# SAM4s_Schematic.net
KiCad netlist of a schematic drawn in Altium Designer
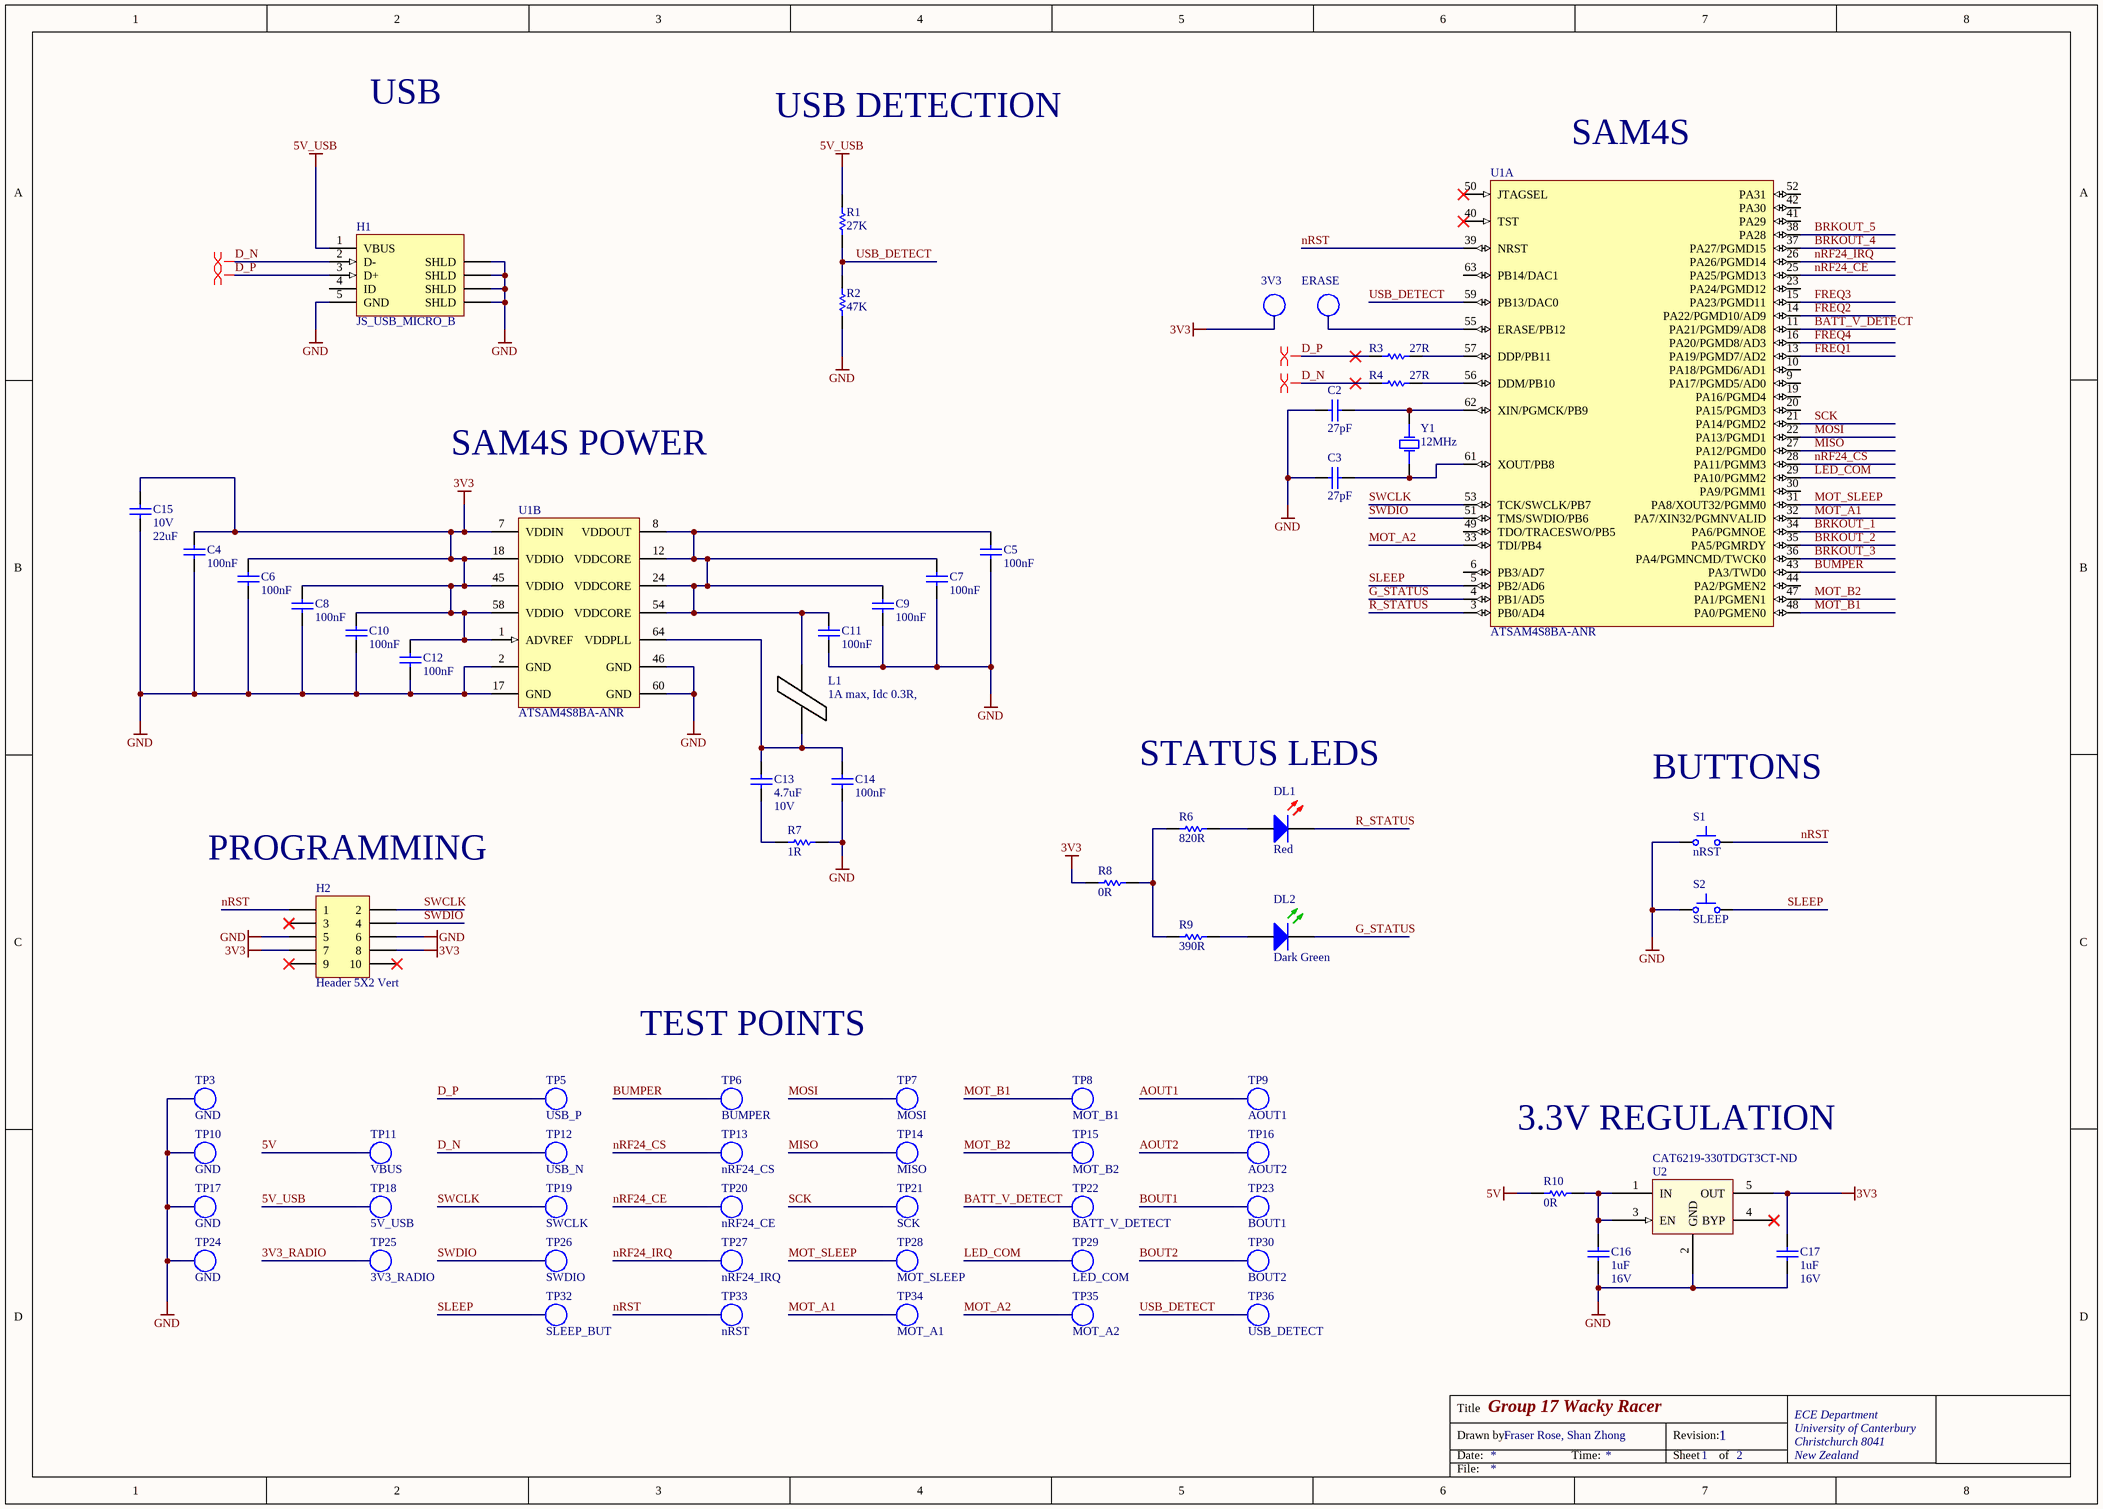
[diagram p0: SAM4s_Schematic.SchDoc]

(export (version "E")
  (design (tool "Eeschema 10.0.6"))
  (components
    (comp (ref "C2")
      (value "27pF")
      (footprint "CAPC1608N")
      (description "CAP CER 27pF NPO/COG +-5% 50V 0603")
      (libsource (lib "ECE AD19Components_19V1") (part "CC_27pF_0603"))
    )
    (comp (ref "C3")
      (value "27pF")
      (footprint "CAPC1608N")
      (description "CAP CER 27pF NPO/COG +-5% 50V 0603")
      (libsource (lib "ECE AD19Components_19V1") (part "CC_27pF_0603"))
    )
    (comp (ref "C4")
      (value "100nF")
      (footprint "CAPC1608N")
      (description "CAP CER 100nF X7R +-10% 50V 0603")
      (libsource (lib "ECE AD19Components_19V1") (part "CC_100nF_0603"))
    )
    (comp (ref "C5")
      (value "100nF")
      (footprint "CAPC1608N")
      (description "CAP CER 100nF X7R +-10% 50V 0603")
      (libsource (lib "ECE AD19Components_19V1") (part "CC_100nF_0603"))
    )
    (comp (ref "C6")
      (value "100nF")
      (footprint "CAPC1608N")
      (description "CAP CER 100nF X7R +-10% 50V 0603")
      (libsource (lib "ECE AD19Components_19V1") (part "CC_100nF_0603"))
    )
    (comp (ref "C7")
      (value "100nF")
      (footprint "CAPC1608N")
      (description "CAP CER 100nF X7R +-10% 50V 0603")
      (libsource (lib "ECE AD19Components_19V1") (part "CC_100nF_0603"))
    )
    (comp (ref "C8")
      (value "100nF")
      (footprint "CAPC1608N")
      (description "CAP CER 100nF X7R +-10% 50V 0603")
      (libsource (lib "ECE AD19Components_19V1") (part "CC_100nF_0603"))
    )
    (comp (ref "C9")
      (value "100nF")
      (footprint "CAPC1608N")
      (description "CAP CER 100nF X7R +-10% 50V 0603")
      (libsource (lib "ECE AD19Components_19V1") (part "CC_100nF_0603"))
    )
    (comp (ref "C10")
      (value "100nF")
      (footprint "CAPC1608N")
      (description "CAP CER 100nF X7R +-10% 50V 0603")
      (libsource (lib "ECE AD19Components_19V1") (part "CC_100nF_0603"))
    )
    (comp (ref "C11")
      (value "100nF")
      (footprint "CAPC1608N")
      (description "CAP CER 100nF X7R +-10% 50V 0603")
      (libsource (lib "ECE AD19Components_19V1") (part "CC_100nF_0603"))
    )
    (comp (ref "C12")
      (value "100nF")
      (footprint "CAPC1608N")
      (description "CAP CER 100nF X7R +-10% 50V 0603")
      (libsource (lib "ECE AD19Components_19V1") (part "CC_100nF_0603"))
    )
    (comp (ref "C13")
      (value "4.7uF")
      (footprint "CAPC1608N")
      (description "CAP CER 4.7uF X5R +-20%  10V 0603")
      (fields (field (name "MAX VOLTAGE") "10V"))
      (libsource (lib "ECE AD19Components_19V1") (part "CC_4.7uF_0603"))
    )
    (comp (ref "C14")
      (value "100nF")
      (footprint "CAPC1608N")
      (description "CAP CER 100nF X7R +-10% 50V 0603")
      (libsource (lib "ECE AD19Components_19V1") (part "CC_100nF_0603"))
    )
    (comp (ref "C15")
      (value "22uF")
      (footprint "CAPC3216N")
      (description "CAP CER 22uF Y5V -20% +80% 10V 1206")
      (fields (field (name "MAX VOLTAGE") "10V"))
      (libsource (lib "ECE AD19Components_19V1") (part "CC_22uF_1206"))
    )
    (comp (ref "C16")
      (value "1uF")
      (footprint "CAPC1608N")
      (description "CAP CER 1uF Y5V -20% +80% 16V 0603")
      (fields (field (name "MAX VOLTAGE") "16V"))
      (libsource (lib "ECE AD19Components_19V1") (part "CC_1uF_0603"))
    )
    (comp (ref "C17")
      (value "1uF")
      (footprint "CAPC1608N")
      (description "CAP CER 1uF Y5V -20% +80% 16V 0603")
      (fields (field (name "MAX VOLTAGE") "16V"))
      (libsource (lib "ECE AD19Components_19V1") (part "CC_1uF_0603"))
    )
    (comp (ref "DL1")
      (value "Red")
      (footprint "WL-SMCW0603")
      (description "LED Red 250mcd 0603 SMD")
      (fields
        (field (name "MANUFACTURER") "WURTH ELEKTRONIK")
        (field (name "MANUFACTURER PART NUMBER") "150060RS75000")
        (field (name "LED COLOUR") "Red")
      )
      (libsource (lib "ECE AD19Components_19V1") (part "DL_150060RS75000"))
    )
    (comp (ref "DL2")
      (value "Dark Green")
      (footprint "WL-SMCW0603")
      (description "LED Dk Green 430mcd 0603 SMD")
      (fields
        (field (name "MANUFACTURER") "WURTH ELEKTRONIK")
        (field (name "MANUFACTURER PART NUMBER") "150060GS75000")
        (field (name "LED COLOUR") "Dark Green")
      )
      (libsource (lib "ECE AD19Components_19V1") (part "DL_150060GS75000"))
    )
    (comp (ref "H1")
      (value "JS_USB_MICRO_B")
      (footprint "FCI_USB_10118194-0001LF")
      (description "CONN USB MICRO B RECPT SMT R/A")
      (fields (field (name "MANUFACTURER") "FCI") (field (name "MANUFACTURER PART NUMBER") "10118194-0001LF"))
      (libsource (lib "ECE AD19Components_19V1") (part "JS_USB_MICRO_B_SMT"))
    )
    (comp (ref "H2")
      (value "Header 5X2 Vert")
      (footprint "IDC2.54-V10D")
      (description "IDC Header, 2,54mm, 10-Pin, Vert")
      (libsource (lib "ECE AD19Components_19V1") (part "JA_HDR_IDC_5X2_VERT"))
    )
    (comp (ref "L1")
      (value "1A max, Idc 0.3R,")
      (footprint "INDC3216N")
      (description "Ferrite Bead, Rdc 0.3R, Z100MHZ 600R, Imax 1A, SMD 1206")
      (fields
        (field (name "MANUFACTURER") "FAIR-RITE")
        (field (name "MANUFACTURER PART NUMBER") "2512066017Y1")
      )
      (libsource (lib "ECE AD19Components_19V1") (part "IN_Ferrite-Bead"))
    )
    (comp (ref "R1")
      (value "27K")
      (footprint "RESC1608N")
      (description "RES 27K OHM 1/10W 5% 0603 SMD")
      (libsource (lib "ECE AD19Components_19V1") (part "RS_27K"))
    )
    (comp (ref "R2")
      (value "47K")
      (footprint "RESC1608N")
      (description "RES 47.0K OHM 1/10W 5% 0603 SMD")
      (libsource (lib "ECE AD19Components_19V1") (part "RS_47K"))
    )
    (comp (ref "R3")
      (value "27R")
      (footprint "RESC1608N")
      (description "RES 27 OHM 1/10W 5% 0603 SMD")
      (libsource (lib "ECE AD19Components_19V1") (part "RS_27R"))
    )
    (comp (ref "R4")
      (value "27R")
      (footprint "RESC1608N")
      (description "RES 27 OHM 1/10W 5% 0603 SMD")
      (libsource (lib "ECE AD19Components_19V1") (part "RS_27R"))
    )
    (comp (ref "R6")
      (value "820R")
      (footprint "RESC1608N")
      (description "RES 820 OHM 1/10W 5% 0603 SMD")
      (libsource (lib "ECE AD19Components_19V1") (part "RS_820R"))
    )
    (comp (ref "R7")
      (value "1R")
      (footprint "RESC3216N")
      (description "RES 1R OHM 1/4W 5% 1206 SMD")
      (libsource (lib "ECE AD19Components_19V1") (part "RT_1R"))
    )
    (comp (ref "R8")
      (value "0R")
      (footprint "RESC1608N")
      (description "RES 0.0 OHM 1/10W 5% 0603 SMD")
      (libsource (lib "ECE AD19Components_19V1") (part "RS_0R0"))
    )
    (comp (ref "R9")
      (value "390R")
      (footprint "RESC1608N")
      (description "RES 390 OHM 1/10W 5% 0603 SMD")
      (libsource (lib "ECE AD19Components_19V1") (part "RS_390R"))
    )
    (comp (ref "R10")
      (value "0R")
      (footprint "RESC1608N")
      (description "RES 0.0 OHM 1/10W 5% 0603 SMD")
      (libsource (lib "ECE AD19Components_19V1") (part "RS_0R0"))
    )
    (comp (ref "S1")
      (value "nRST")
      (footprint "EVQPNF05M")
      (description "Panasonic 6 x 3.5mm SMD Light Touch Switch Type SMD")
      (fields (field (name "MANUFACTURER") "Panasonic"))
      (libsource (lib "ECE AD19Components_19V1") (part "WS_EVQPNF05M"))
    )
    (comp (ref "S2")
      (value "SLEEP")
      (footprint "EVQPNF05M")
      (description "Panasonic 6 x 3.5mm SMD Light Touch Switch Type SMD")
      (fields (field (name "MANUFACTURER") "Panasonic"))
      (libsource (lib "ECE AD19Components_19V1") (part "WS_EVQPNF05M"))
    )
    (comp (ref "TP1")
      (value "3V3")
      (footprint "TP_0603")
      (description "Test Point 1.65X0.9X1.2mm SMD")
      (fields
        (field (name "MANUFACTURER") "TE Connectivity AMP Connectors")
        (field (name "MANUFACTURER PART NUMBER") "1625854-3")
      )
      (libsource (lib "ECE AD19Components_19V1") (part "TP_0603"))
    )
    (comp (ref "TP2")
      (value "ERASE")
      (footprint "TP_0603")
      (description "Test Point 1.65X0.9X1.2mm SMD")
      (fields
        (field (name "MANUFACTURER") "TE Connectivity AMP Connectors")
        (field (name "MANUFACTURER PART NUMBER") "1625854-3")
      )
      (libsource (lib "ECE AD19Components_19V1") (part "TP_0603"))
    )
    (comp (ref "TP3")
      (value "GND")
      (footprint "TP_0603")
      (description "Test Point 1.65X0.9X1.2mm SMD")
      (fields
        (field (name "MANUFACTURER") "TE Connectivity AMP Connectors")
        (field (name "MANUFACTURER PART NUMBER") "1625854-3")
      )
      (libsource (lib "ECE AD19Components_19V1") (part "TP_0603"))
    )
    (comp (ref "TP5")
      (value "USB_P")
      (footprint "TP_0603")
      (description "Test Point 1.65X0.9X1.2mm SMD")
      (fields
        (field (name "MANUFACTURER") "TE Connectivity AMP Connectors")
        (field (name "MANUFACTURER PART NUMBER") "1625854-3")
      )
      (libsource (lib "ECE AD19Components_19V1") (part "TP_0603"))
    )
    (comp (ref "TP6")
      (value "BUMPER")
      (footprint "TP_0603")
      (description "Test Point 1.65X0.9X1.2mm SMD")
      (fields
        (field (name "MANUFACTURER") "TE Connectivity AMP Connectors")
        (field (name "MANUFACTURER PART NUMBER") "1625854-3")
      )
      (libsource (lib "ECE AD19Components_19V1") (part "TP_0603"))
    )
    (comp (ref "TP7")
      (value "MOSI")
      (footprint "TP_0603")
      (description "Test Point 1.65X0.9X1.2mm SMD")
      (fields
        (field (name "MANUFACTURER") "TE Connectivity AMP Connectors")
        (field (name "MANUFACTURER PART NUMBER") "1625854-3")
      )
      (libsource (lib "ECE AD19Components_19V1") (part "TP_0603"))
    )
    (comp (ref "TP8")
      (value "MOT_B1")
      (footprint "TP_0603")
      (description "Test Point 1.65X0.9X1.2mm SMD")
      (fields
        (field (name "MANUFACTURER") "TE Connectivity AMP Connectors")
        (field (name "MANUFACTURER PART NUMBER") "1625854-3")
      )
      (libsource (lib "ECE AD19Components_19V1") (part "TP_0603"))
    )
    (comp (ref "TP9")
      (value "AOUT1")
      (footprint "TP_0603")
      (description "Test Point 1.65X0.9X1.2mm SMD")
      (fields
        (field (name "MANUFACTURER") "TE Connectivity AMP Connectors")
        (field (name "MANUFACTURER PART NUMBER") "1625854-3")
      )
      (libsource (lib "ECE AD19Components_19V1") (part "TP_0603"))
    )
    (comp (ref "TP10")
      (value "GND")
      (footprint "TP_0603")
      (description "Test Point 1.65X0.9X1.2mm SMD")
      (fields
        (field (name "MANUFACTURER") "TE Connectivity AMP Connectors")
        (field (name "MANUFACTURER PART NUMBER") "1625854-3")
      )
      (libsource (lib "ECE AD19Components_19V1") (part "TP_0603"))
    )
    (comp (ref "TP11")
      (value "VBUS")
      (footprint "TP_0603")
      (description "Test Point 1.65X0.9X1.2mm SMD")
      (fields
        (field (name "MANUFACTURER") "TE Connectivity AMP Connectors")
        (field (name "MANUFACTURER PART NUMBER") "1625854-3")
      )
      (libsource (lib "ECE AD19Components_19V1") (part "TP_0603"))
    )
    (comp (ref "TP12")
      (value "USB_N")
      (footprint "TP_0603")
      (description "Test Point 1.65X0.9X1.2mm SMD")
      (fields
        (field (name "MANUFACTURER") "TE Connectivity AMP Connectors")
        (field (name "MANUFACTURER PART NUMBER") "1625854-3")
      )
      (libsource (lib "ECE AD19Components_19V1") (part "TP_0603"))
    )
    (comp (ref "TP13")
      (value "nRF24_CS")
      (footprint "TP_0603")
      (description "Test Point 1.65X0.9X1.2mm SMD")
      (fields
        (field (name "MANUFACTURER") "TE Connectivity AMP Connectors")
        (field (name "MANUFACTURER PART NUMBER") "1625854-3")
      )
      (libsource (lib "ECE AD19Components_19V1") (part "TP_0603"))
    )
    (comp (ref "TP14")
      (value "MISO")
      (footprint "TP_0603")
      (description "Test Point 1.65X0.9X1.2mm SMD")
      (fields
        (field (name "MANUFACTURER") "TE Connectivity AMP Connectors")
        (field (name "MANUFACTURER PART NUMBER") "1625854-3")
      )
      (libsource (lib "ECE AD19Components_19V1") (part "TP_0603"))
    )
    (comp (ref "TP15")
      (value "MOT_B2")
      (footprint "TP_0603")
      (description "Test Point 1.65X0.9X1.2mm SMD")
      (fields
        (field (name "MANUFACTURER") "TE Connectivity AMP Connectors")
        (field (name "MANUFACTURER PART NUMBER") "1625854-3")
      )
      (libsource (lib "ECE AD19Components_19V1") (part "TP_0603"))
    )
    (comp (ref "TP16")
      (value "AOUT2")
      (footprint "TP_0603")
      (description "Test Point 1.65X0.9X1.2mm SMD")
      (fields
        (field (name "MANUFACTURER") "TE Connectivity AMP Connectors")
        (field (name "MANUFACTURER PART NUMBER") "1625854-3")
      )
      (libsource (lib "ECE AD19Components_19V1") (part "TP_0603"))
    )
    (comp (ref "TP17")
      (value "GND")
      (footprint "TP_0603")
      (description "Test Point 1.65X0.9X1.2mm SMD")
      (fields
        (field (name "MANUFACTURER") "TE Connectivity AMP Connectors")
        (field (name "MANUFACTURER PART NUMBER") "1625854-3")
      )
      (libsource (lib "ECE AD19Components_19V1") (part "TP_0603"))
    )
    (comp (ref "TP18")
      (value "5V_USB")
      (footprint "TP_0603")
      (description "Test Point 1.65X0.9X1.2mm SMD")
      (fields
        (field (name "MANUFACTURER") "TE Connectivity AMP Connectors")
        (field (name "MANUFACTURER PART NUMBER") "1625854-3")
      )
      (libsource (lib "ECE AD19Components_19V1") (part "TP_0603"))
    )
    (comp (ref "TP19")
      (value "SWCLK")
      (footprint "TP_0603")
      (description "Test Point 1.65X0.9X1.2mm SMD")
      (fields
        (field (name "MANUFACTURER") "TE Connectivity AMP Connectors")
        (field (name "MANUFACTURER PART NUMBER") "1625854-3")
      )
      (libsource (lib "ECE AD19Components_19V1") (part "TP_0603"))
    )
    (comp (ref "TP20")
      (value "nRF24_CE")
      (footprint "TP_0603")
      (description "Test Point 1.65X0.9X1.2mm SMD")
      (fields
        (field (name "MANUFACTURER") "TE Connectivity AMP Connectors")
        (field (name "MANUFACTURER PART NUMBER") "1625854-3")
      )
      (libsource (lib "ECE AD19Components_19V1") (part "TP_0603"))
    )
    (comp (ref "TP21")
      (value "SCK")
      (footprint "TP_0603")
      (description "Test Point 1.65X0.9X1.2mm SMD")
      (fields
        (field (name "MANUFACTURER") "TE Connectivity AMP Connectors")
        (field (name "MANUFACTURER PART NUMBER") "1625854-3")
      )
      (libsource (lib "ECE AD19Components_19V1") (part "TP_0603"))
    )
    (comp (ref "TP22")
      (value "BATT_V_DETECT")
      (footprint "TP_0603")
      (description "Test Point 1.65X0.9X1.2mm SMD")
      (fields
        (field (name "MANUFACTURER") "TE Connectivity AMP Connectors")
        (field (name "MANUFACTURER PART NUMBER") "1625854-3")
      )
      (libsource (lib "ECE AD19Components_19V1") (part "TP_0603"))
    )
    (comp (ref "TP23")
      (value "BOUT1")
      (footprint "TP_0603")
      (description "Test Point 1.65X0.9X1.2mm SMD")
      (fields
        (field (name "MANUFACTURER") "TE Connectivity AMP Connectors")
        (field (name "MANUFACTURER PART NUMBER") "1625854-3")
      )
      (libsource (lib "ECE AD19Components_19V1") (part "TP_0603"))
    )
    (comp (ref "TP24")
      (value "GND")
      (footprint "TP_0603")
      (description "Test Point 1.65X0.9X1.2mm SMD")
      (fields
        (field (name "MANUFACTURER") "TE Connectivity AMP Connectors")
        (field (name "MANUFACTURER PART NUMBER") "1625854-3")
      )
      (libsource (lib "ECE AD19Components_19V1") (part "TP_0603"))
    )
    (comp (ref "TP25")
      (value "3V3_RADIO")
      (footprint "TP_0603")
      (description "Test Point 1.65X0.9X1.2mm SMD")
      (fields
        (field (name "MANUFACTURER") "TE Connectivity AMP Connectors")
        (field (name "MANUFACTURER PART NUMBER") "1625854-3")
      )
      (libsource (lib "ECE AD19Components_19V1") (part "TP_0603"))
    )
    (comp (ref "TP26")
      (value "SWDIO")
      (footprint "TP_0603")
      (description "Test Point 1.65X0.9X1.2mm SMD")
      (fields
        (field (name "MANUFACTURER") "TE Connectivity AMP Connectors")
        (field (name "MANUFACTURER PART NUMBER") "1625854-3")
      )
      (libsource (lib "ECE AD19Components_19V1") (part "TP_0603"))
    )
    (comp (ref "TP27")
      (value "nRF24_IRQ")
      (footprint "TP_0603")
      (description "Test Point 1.65X0.9X1.2mm SMD")
      (fields
        (field (name "MANUFACTURER") "TE Connectivity AMP Connectors")
        (field (name "MANUFACTURER PART NUMBER") "1625854-3")
      )
      (libsource (lib "ECE AD19Components_19V1") (part "TP_0603"))
    )
    (comp (ref "TP28")
      (value "MOT_SLEEP")
      (footprint "TP_0603")
      (description "Test Point 1.65X0.9X1.2mm SMD")
      (fields
        (field (name "MANUFACTURER") "TE Connectivity AMP Connectors")
        (field (name "MANUFACTURER PART NUMBER") "1625854-3")
      )
      (libsource (lib "ECE AD19Components_19V1") (part "TP_0603"))
    )
    (comp (ref "TP29")
      (value "LED_COM")
      (footprint "TP_0603")
      (description "Test Point 1.65X0.9X1.2mm SMD")
      (fields
        (field (name "MANUFACTURER") "TE Connectivity AMP Connectors")
        (field (name "MANUFACTURER PART NUMBER") "1625854-3")
      )
      (libsource (lib "ECE AD19Components_19V1") (part "TP_0603"))
    )
    (comp (ref "TP30")
      (value "BOUT2")
      (footprint "TP_0603")
      (description "Test Point 1.65X0.9X1.2mm SMD")
      (fields
        (field (name "MANUFACTURER") "TE Connectivity AMP Connectors")
        (field (name "MANUFACTURER PART NUMBER") "1625854-3")
      )
      (libsource (lib "ECE AD19Components_19V1") (part "TP_0603"))
    )
    (comp (ref "TP32")
      (value "SLEEP_BUT")
      (footprint "TP_0603")
      (description "Test Point 1.65X0.9X1.2mm SMD")
      (fields
        (field (name "MANUFACTURER") "TE Connectivity AMP Connectors")
        (field (name "MANUFACTURER PART NUMBER") "1625854-3")
      )
      (libsource (lib "ECE AD19Components_19V1") (part "TP_0603"))
    )
    (comp (ref "TP33")
      (value "nRST")
      (footprint "TP_0603")
      (description "Test Point 1.65X0.9X1.2mm SMD")
      (fields
        (field (name "MANUFACTURER") "TE Connectivity AMP Connectors")
        (field (name "MANUFACTURER PART NUMBER") "1625854-3")
      )
      (libsource (lib "ECE AD19Components_19V1") (part "TP_0603"))
    )
    (comp (ref "TP34")
      (value "MOT_A1")
      (footprint "TP_0603")
      (description "Test Point 1.65X0.9X1.2mm SMD")
      (fields
        (field (name "MANUFACTURER") "TE Connectivity AMP Connectors")
        (field (name "MANUFACTURER PART NUMBER") "1625854-3")
      )
      (libsource (lib "ECE AD19Components_19V1") (part "TP_0603"))
    )
    (comp (ref "TP35")
      (value "MOT_A2")
      (footprint "TP_0603")
      (description "Test Point 1.65X0.9X1.2mm SMD")
      (fields
        (field (name "MANUFACTURER") "TE Connectivity AMP Connectors")
        (field (name "MANUFACTURER PART NUMBER") "1625854-3")
      )
      (libsource (lib "ECE AD19Components_19V1") (part "TP_0603"))
    )
    (comp (ref "TP36")
      (value "USB_DETECT")
      (footprint "TP_0603")
      (description "Test Point 1.65X0.9X1.2mm SMD")
      (fields
        (field (name "MANUFACTURER") "TE Connectivity AMP Connectors")
        (field (name "MANUFACTURER PART NUMBER") "1625854-3")
      )
      (libsource (lib "ECE AD19Components_19V1") (part "TP_0603"))
    )
    (comp (ref "U1")
      (value "ATSAM4S8BA-ANR")
      (footprint "LQFP64_L")
      (description "IC MCU 32BIT 512KB FLASH 64LQFP")
      (fields (field (name "MANUFACTURER") "Atmel"))
      (libsource (lib "ECE AD19Components_19V1") (part "SE_ATSAM4S16BA-MU"))
    )
    (comp (ref "U2")
      (value "CAT6219-330TDGT3")
      (footprint "SOT95P280X145-5N")
      (description "IC REG LIN 3.3V 500MA TSOT23-5")
      (fields
        (field (name "BASE PART NUMBER") "CAT6219")
        (field (name "SUPPLIER PART NUMBER") "CAT6219-330TDGT3CT-ND")
      )
      (libsource (lib "ENCE461AD19_19V2") (part "SV_CAT6219-330TDGT3"))
    )
    (comp (ref "Y1")
      (value "12MHz")
      (footprint "6.0X3.5-4")
      (description "CRYSTAL 12MHZ 18PF 6X3.5mm SMD")
      (fields
        (field (name "MANUFACTURER") "CTS-Frequency Controls")
        (field (name "MANUFACTURER PART NUMBER") "406C35D12M00000")
        (field (name "FREQUENCY") "12MHz")
      )
      (libsource (lib "ECE AD19Components_19V1") (part "XT_CRYSTAL_12MHz_18pF"))
    )
  )
  (nets
    (net (code "1") (name "/3V3_RADIO") (class "Default")
      (node (ref "TP25") (pin "1") (pinfunction "TP_1") (pintype "passive"))
    )
    (net (code "2") (name "/AOUT1") (class "Default")
      (node (ref "TP9") (pin "1") (pinfunction "TP_1") (pintype "passive"))
    )
    (net (code "3") (name "/AOUT2") (class "Default")
      (node (ref "TP16") (pin "1") (pinfunction "TP_1") (pintype "passive"))
    )
    (net (code "4") (name "/BATT_V_DETECT") (class "Default")
      (node (ref "TP22") (pin "1") (pinfunction "TP_1") (pintype "passive"))
      (node (ref "U1") (pin "11") (pinfunction "PA21/PGMD9/AD8_11") (pintype "bidirectional"))
    )
    (net (code "5") (name "/BOUT1") (class "Default")
      (node (ref "TP23") (pin "1") (pinfunction "TP_1") (pintype "passive"))
    )
    (net (code "6") (name "/BOUT2") (class "Default")
      (node (ref "TP30") (pin "1") (pinfunction "TP_1") (pintype "passive"))
    )
    (net (code "7") (name "/BRKOUT_1") (class "Default")
      (node (ref "U1") (pin "34") (pinfunction "PA6/PGMNOE_34") (pintype "bidirectional"))
    )
    (net (code "8") (name "/BRKOUT_2") (class "Default")
      (node (ref "U1") (pin "35") (pinfunction "PA5/PGMRDY_35") (pintype "bidirectional"))
    )
    (net (code "9") (name "/BRKOUT_3") (class "Default")
      (node (ref "U1") (pin "36") (pinfunction "PA4/PGMNCMD/TWCK0_36") (pintype "bidirectional"))
    )
    (net (code "10") (name "/BRKOUT_4") (class "Default")
      (node (ref "U1") (pin "37") (pinfunction "PA27/PGMD15_37") (pintype "bidirectional"))
    )
    (net (code "11") (name "/BRKOUT_5") (class "Default")
      (node (ref "U1") (pin "38") (pinfunction "PA28_38") (pintype "bidirectional"))
    )
    (net (code "12") (name "/BUMPER") (class "Default")
      (node (ref "TP6") (pin "1") (pinfunction "TP_1") (pintype "passive"))
      (node (ref "U1") (pin "43") (pinfunction "PA3/TWD0_43") (pintype "bidirectional"))
    )
    (net (code "13") (name "/D_N") (class "Default")
      (node (ref "H1") (pin "2") (pinfunction "D-_2") (pintype "input"))
      (node (ref "R4") (pin "1") (pinfunction "1_1") (pintype "passive"))
      (node (ref "TP12") (pin "1") (pinfunction "TP_1") (pintype "passive"))
    )
    (net (code "14") (name "/D_P") (class "Default")
      (node (ref "H1") (pin "3") (pinfunction "D+_3") (pintype "input"))
      (node (ref "R3") (pin "1") (pinfunction "1_1") (pintype "passive"))
      (node (ref "TP5") (pin "1") (pinfunction "TP_1") (pintype "passive"))
    )
    (net (code "15") (name "/FREQ1") (class "Default")
      (node (ref "U1") (pin "13") (pinfunction "PA19/PGMD7/AD2_13") (pintype "bidirectional"))
    )
    (net (code "16") (name "/FREQ2") (class "Default")
      (node (ref "U1") (pin "14") (pinfunction "PA22/PGMD10/AD9_14") (pintype "bidirectional"))
    )
    (net (code "17") (name "/FREQ3") (class "Default")
      (node (ref "U1") (pin "15") (pinfunction "PA23/PGMD11_15") (pintype "bidirectional"))
    )
    (net (code "18") (name "/FREQ4") (class "Default")
      (node (ref "U1") (pin "16") (pinfunction "PA20/PGMD8/AD3_16") (pintype "bidirectional"))
    )
    (net (code "19") (name "/G_STATUS") (class "Default")
      (node (ref "DL2") (pin "1") (pinfunction "K_1") (pintype "passive"))
      (node (ref "U1") (pin "4") (pinfunction "PB1/AD5_4") (pintype "bidirectional"))
    )
    (net (code "20") (name "/LED_COM") (class "Default")
      (node (ref "TP29") (pin "1") (pinfunction "TP_1") (pintype "passive"))
      (node (ref "U1") (pin "29") (pinfunction "PA10/PGMM2_29") (pintype "bidirectional"))
    )
    (net (code "21") (name "/MISO") (class "Default")
      (node (ref "TP14") (pin "1") (pinfunction "TP_1") (pintype "passive"))
      (node (ref "U1") (pin "27") (pinfunction "PA12/PGMD0_27") (pintype "bidirectional"))
    )
    (net (code "22") (name "/MOSI") (class "Default")
      (node (ref "TP7") (pin "1") (pinfunction "TP_1") (pintype "passive"))
      (node (ref "U1") (pin "22") (pinfunction "PA13/PGMD1_22") (pintype "bidirectional"))
    )
    (net (code "23") (name "/MOT_A1") (class "Default")
      (node (ref "TP34") (pin "1") (pinfunction "TP_1") (pintype "passive"))
      (node (ref "U1") (pin "32") (pinfunction "PA7/XIN32/PGMNVALID_32") (pintype "bidirectional"))
    )
    (net (code "24") (name "/MOT_A2") (class "Default")
      (node (ref "TP35") (pin "1") (pinfunction "TP_1") (pintype "passive"))
      (node (ref "U1") (pin "33") (pinfunction "TDI/PB4_33") (pintype "bidirectional"))
    )
    (net (code "25") (name "/MOT_B1") (class "Default")
      (node (ref "TP8") (pin "1") (pinfunction "TP_1") (pintype "passive"))
      (node (ref "U1") (pin "48") (pinfunction "PA0/PGMEN0_48") (pintype "bidirectional"))
    )
    (net (code "26") (name "/MOT_B2") (class "Default")
      (node (ref "TP15") (pin "1") (pinfunction "TP_1") (pintype "passive"))
      (node (ref "U1") (pin "47") (pinfunction "PA1/PGMEN1_47") (pintype "bidirectional"))
    )
    (net (code "27") (name "/MOT_SLEEP") (class "Default")
      (node (ref "TP28") (pin "1") (pinfunction "TP_1") (pintype "passive"))
      (node (ref "U1") (pin "31") (pinfunction "PA8/XOUT32/PGMM0_31") (pintype "bidirectional"))
    )
    (net (code "28") (name "/R_STATUS") (class "Default")
      (node (ref "DL1") (pin "1") (pinfunction "K_1") (pintype "passive"))
      (node (ref "U1") (pin "3") (pinfunction "PB0/AD4_3") (pintype "bidirectional"))
    )
    (net (code "29") (name "/SCK") (class "Default")
      (node (ref "TP21") (pin "1") (pinfunction "TP_1") (pintype "passive"))
      (node (ref "U1") (pin "21") (pinfunction "PA14/PGMD2_21") (pintype "bidirectional"))
    )
    (net (code "30") (name "/SLEEP") (class "Default")
      (node (ref "S2") (pin "2") (pintype "passive"))
      (node (ref "TP32") (pin "1") (pinfunction "TP_1") (pintype "passive"))
      (node (ref "U1") (pin "5") (pinfunction "PB2/AD6_5") (pintype "bidirectional"))
    )
    (net (code "31") (name "/SWCLK") (class "Default")
      (node (ref "H2") (pin "2") (pinfunction "2_2") (pintype "passive"))
      (node (ref "TP19") (pin "1") (pinfunction "TP_1") (pintype "passive"))
      (node (ref "U1") (pin "53") (pinfunction "TCK/SWCLK/PB7_53") (pintype "bidirectional"))
    )
    (net (code "32") (name "/SWDIO") (class "Default")
      (node (ref "H2") (pin "4") (pinfunction "4_4") (pintype "passive"))
      (node (ref "TP26") (pin "1") (pinfunction "TP_1") (pintype "passive"))
      (node (ref "U1") (pin "51") (pinfunction "TMS/SWDIO/PB6_51") (pintype "bidirectional"))
    )
    (net (code "33") (name "/USB_DETECT") (class "Default")
      (node (ref "R1") (pin "1") (pinfunction "1_1") (pintype "passive"))
      (node (ref "R2") (pin "2") (pinfunction "2_2") (pintype "passive"))
      (node (ref "TP36") (pin "1") (pinfunction "TP_1") (pintype "passive"))
      (node (ref "U1") (pin "59") (pinfunction "PB13/DAC0_59") (pintype "bidirectional"))
    )
    (net (code "34") (name "/nRF24_CE") (class "Default")
      (node (ref "TP20") (pin "1") (pinfunction "TP_1") (pintype "passive"))
      (node (ref "U1") (pin "25") (pinfunction "PA25/PGMD13_25") (pintype "bidirectional"))
    )
    (net (code "35") (name "/nRF24_CS") (class "Default")
      (node (ref "TP13") (pin "1") (pinfunction "TP_1") (pintype "passive"))
      (node (ref "U1") (pin "28") (pinfunction "PA11/PGMM3_28") (pintype "bidirectional"))
    )
    (net (code "36") (name "/nRF24_IRQ") (class "Default")
      (node (ref "TP27") (pin "1") (pinfunction "TP_1") (pintype "passive"))
      (node (ref "U1") (pin "26") (pinfunction "PA26/PGMD14_26") (pintype "bidirectional"))
    )
    (net (code "37") (name "/nRST") (class "Default")
      (node (ref "H2") (pin "1") (pinfunction "1_1") (pintype "passive"))
      (node (ref "S1") (pin "2") (pintype "passive"))
      (node (ref "TP33") (pin "1") (pinfunction "TP_1") (pintype "passive"))
      (node (ref "U1") (pin "39") (pinfunction "NRST_39") (pintype "bidirectional"))
    )
    (net (code "38") (name "3V3") (class "Default")
      (node (ref "C10") (pin "2") (pinfunction "2_2") (pintype "passive"))
      (node (ref "C12") (pin "2") (pinfunction "2_2") (pintype "passive"))
      (node (ref "C15") (pin "2") (pinfunction "2_2") (pintype "passive"))
      (node (ref "C17") (pin "2") (pinfunction "2_2") (pintype "passive"))
      (node (ref "C4") (pin "2") (pinfunction "2_2") (pintype "passive"))
      (node (ref "C6") (pin "2") (pinfunction "2_2") (pintype "passive"))
      (node (ref "C8") (pin "2") (pinfunction "2_2") (pintype "passive"))
      (node (ref "H2") (pin "7") (pinfunction "7_7") (pintype "passive"))
      (node (ref "H2") (pin "8") (pinfunction "8_8") (pintype "passive"))
      (node (ref "R8") (pin "2") (pinfunction "2_2") (pintype "passive"))
      (node (ref "TP1") (pin "1") (pinfunction "TP_1") (pintype "passive"))
      (node (ref "U1") (pin "1") (pinfunction "ADVREF_1") (pintype "input"))
      (node (ref "U1") (pin "18") (pinfunction "VDDIO_18") (pintype "power_in"))
      (node (ref "U1") (pin "45") (pinfunction "VDDIO_45") (pintype "power_in"))
      (node (ref "U1") (pin "58") (pinfunction "VDDIO_58") (pintype "power_in"))
      (node (ref "U1") (pin "7") (pinfunction "VDDIN_7") (pintype "power_in"))
      (node (ref "U2") (pin "5") (pinfunction "OUT_5") (pintype "power_in"))
    )
    (net (code "39") (name "5V") (class "Default")
      (node (ref "R10") (pin "2") (pinfunction "2_2") (pintype "passive"))
      (node (ref "TP11") (pin "1") (pinfunction "TP_1") (pintype "passive"))
    )
    (net (code "40") (name "5V_USB") (class "Default")
      (node (ref "H1") (pin "1") (pinfunction "VBUS_1") (pintype "power_in"))
      (node (ref "R1") (pin "2") (pinfunction "2_2") (pintype "passive"))
      (node (ref "TP18") (pin "1") (pinfunction "TP_1") (pintype "passive"))
    )
    (net (code "41") (name "GND") (class "Default")
      (node (ref "C10") (pin "1") (pinfunction "1_1") (pintype "passive"))
      (node (ref "C11") (pin "1") (pinfunction "1_1") (pintype "passive"))
      (node (ref "C12") (pin "1") (pinfunction "1_1") (pintype "passive"))
      (node (ref "C14") (pin "1") (pinfunction "1_1") (pintype "passive"))
      (node (ref "C15") (pin "1") (pinfunction "1_1") (pintype "passive"))
      (node (ref "C16") (pin "1") (pinfunction "1_1") (pintype "passive"))
      (node (ref "C17") (pin "1") (pinfunction "1_1") (pintype "passive"))
      (node (ref "C2") (pin "1") (pinfunction "1_1") (pintype "passive"))
      (node (ref "C3") (pin "1") (pinfunction "1_1") (pintype "passive"))
      (node (ref "C4") (pin "1") (pinfunction "1_1") (pintype "passive"))
      (node (ref "C5") (pin "1") (pinfunction "1_1") (pintype "passive"))
      (node (ref "C6") (pin "1") (pinfunction "1_1") (pintype "passive"))
      (node (ref "C7") (pin "1") (pinfunction "1_1") (pintype "passive"))
      (node (ref "C8") (pin "1") (pinfunction "1_1") (pintype "passive"))
      (node (ref "C9") (pin "1") (pinfunction "1_1") (pintype "passive"))
      (node (ref "H1") (pin "5") (pinfunction "GND_5") (pintype "passive"))
      (node (ref "H1") (pin "6") (pinfunction "SHLD_6") (pintype "passive"))
      (node (ref "H2") (pin "5") (pinfunction "5_5") (pintype "passive"))
      (node (ref "H2") (pin "6") (pinfunction "6_6") (pintype "passive"))
      (node (ref "R2") (pin "1") (pinfunction "1_1") (pintype "passive"))
      (node (ref "R7") (pin "1") (pinfunction "1_1") (pintype "passive"))
      (node (ref "S1") (pin "1") (pintype "passive"))
      (node (ref "S2") (pin "1") (pintype "passive"))
      (node (ref "TP10") (pin "1") (pinfunction "TP_1") (pintype "passive"))
      (node (ref "TP17") (pin "1") (pinfunction "TP_1") (pintype "passive"))
      (node (ref "TP24") (pin "1") (pinfunction "TP_1") (pintype "passive"))
      (node (ref "TP3") (pin "1") (pinfunction "TP_1") (pintype "passive"))
      (node (ref "U1") (pin "17") (pinfunction "GND_17") (pintype "power_in"))
      (node (ref "U1") (pin "2") (pinfunction "GND_2") (pintype "power_in"))
      (node (ref "U1") (pin "46") (pinfunction "GND_46") (pintype "power_in"))
      (node (ref "U1") (pin "60") (pinfunction "GND_60") (pintype "power_in"))
      (node (ref "U2") (pin "2") (pinfunction "GND_2") (pintype "power_in"))
    )
    (net (code "42") (name "Net-(C13-Pad1)") (class "Default")
      (node (ref "C13") (pin "1") (pinfunction "1_1") (pintype "passive"))
      (node (ref "R7") (pin "2") (pinfunction "2_2") (pintype "passive"))
    )
    (net (code "43") (name "Net-(DL1-A)") (class "Default")
      (node (ref "DL1") (pin "2") (pinfunction "A_2") (pintype "passive"))
      (node (ref "R6") (pin "1") (pinfunction "1_1") (pintype "passive"))
    )
    (net (code "44") (name "Net-(DL2-A)") (class "Default")
      (node (ref "DL2") (pin "2") (pinfunction "A_2") (pintype "passive"))
      (node (ref "R9") (pin "2") (pinfunction "2_2") (pintype "passive"))
    )
    (net (code "45") (name "Net-(R6-Pad2)") (class "Default")
      (node (ref "R6") (pin "2") (pinfunction "2_2") (pintype "passive"))
      (node (ref "R8") (pin "1") (pinfunction "1_1") (pintype "passive"))
      (node (ref "R9") (pin "1") (pinfunction "1_1") (pintype "passive"))
    )
    (net (code "46") (name "Net-(TP2-TP)") (class "Default")
      (node (ref "TP2") (pin "1") (pinfunction "TP_1") (pintype "passive"))
      (node (ref "U1") (pin "55") (pinfunction "ERASE/PB12_55") (pintype "bidirectional"))
    )
    (net (code "47") (name "Net-(U1A-DDM{slash}PB10)") (class "Default")
      (node (ref "R4") (pin "2") (pinfunction "2_2") (pintype "passive"))
      (node (ref "U1") (pin "56") (pinfunction "DDM/PB10_56") (pintype "bidirectional"))
    )
    (net (code "48") (name "Net-(U1A-DDP{slash}PB11)") (class "Default")
      (node (ref "R3") (pin "2") (pinfunction "2_2") (pintype "passive"))
      (node (ref "U1") (pin "57") (pinfunction "DDP/PB11_57") (pintype "bidirectional"))
    )
    (net (code "49") (name "Net-(U1A-XIN{slash}PGMCK{slash}PB9)") (class "Default")
      (node (ref "C2") (pin "2") (pinfunction "2_2") (pintype "passive"))
      (node (ref "U1") (pin "62") (pinfunction "XIN/PGMCK/PB9_62") (pintype "bidirectional"))
      (node (ref "Y1") (pin "3") (pinfunction "OSC2_3") (pintype "passive"))
    )
    (net (code "50") (name "Net-(U1A-XOUT{slash}PB8)") (class "Default")
      (node (ref "C3") (pin "2") (pinfunction "2_2") (pintype "passive"))
      (node (ref "U1") (pin "61") (pinfunction "XOUT/PB8_61") (pintype "bidirectional"))
      (node (ref "Y1") (pin "1") (pinfunction "OSC1_1") (pintype "passive"))
    )
    (net (code "51") (name "Net-(U1B-VDDOUT)") (class "Default")
      (node (ref "C11") (pin "2") (pinfunction "2_2") (pintype "passive"))
      (node (ref "C5") (pin "2") (pinfunction "2_2") (pintype "passive"))
      (node (ref "C7") (pin "2") (pinfunction "2_2") (pintype "passive"))
      (node (ref "C9") (pin "2") (pinfunction "2_2") (pintype "passive"))
      (node (ref "L1") (pin "2") (pinfunction "2_2") (pintype "passive"))
      (node (ref "U1") (pin "12") (pinfunction "VDDCORE_12") (pintype "power_in"))
      (node (ref "U1") (pin "24") (pinfunction "VDDCORE_24") (pintype "power_in"))
      (node (ref "U1") (pin "54") (pinfunction "VDDCORE_54") (pintype "power_in"))
      (node (ref "U1") (pin "8") (pinfunction "VDDOUT_8") (pintype "power_in"))
    )
    (net (code "52") (name "Net-(U1B-VDDPLL)") (class "Default")
      (node (ref "C13") (pin "2") (pinfunction "2_2") (pintype "passive"))
      (node (ref "C14") (pin "2") (pinfunction "2_2") (pintype "passive"))
      (node (ref "L1") (pin "1") (pinfunction "1_1") (pintype "passive"))
      (node (ref "U1") (pin "64") (pinfunction "VDDPLL_64") (pintype "power_in"))
    )
    (net (code "53") (name "Net-(U2-EN)") (class "Default")
      (node (ref "C16") (pin "2") (pinfunction "2_2") (pintype "passive"))
      (node (ref "R10") (pin "1") (pinfunction "1_1") (pintype "passive"))
      (node (ref "U2") (pin "1") (pinfunction "IN_1") (pintype "power_in"))
      (node (ref "U2") (pin "3") (pinfunction "EN_3") (pintype "input"))
    )
    (net (code "54") (name "unconnected-(H1-ID-Pad4)") (class "Default")
      (node (ref "H1") (pin "4") (pinfunction "ID_4") (pintype "power_in"))
    )
    (net (code "55") (name "unconnected-(H2-Pad3)") (class "Default")
      (node (ref "H2") (pin "3") (pinfunction "3_3") (pintype "passive+no_connect"))
    )
    (net (code "56") (name "unconnected-(H2-Pad9)") (class "Default")
      (node (ref "H2") (pin "9") (pinfunction "9_9") (pintype "passive+no_connect"))
    )
    (net (code "57") (name "unconnected-(H2-Pad10)") (class "Default")
      (node (ref "H2") (pin "10") (pinfunction "10_10") (pintype "passive+no_connect"))
    )
    (net (code "58") (name "unconnected-(U1A-JTAGSEL-Pad50)") (class "Default")
      (node (ref "U1") (pin "50") (pinfunction "JTAGSEL_50") (pintype "input+no_connect"))
    )
    (net (code "59") (name "unconnected-(U1A-PA2{slash}PGMEN2-Pad44)") (class "Default")
      (node (ref "U1") (pin "44") (pinfunction "PA2/PGMEN2_44") (pintype "bidirectional"))
    )
    (net (code "60") (name "unconnected-(U1A-PA9{slash}PGMM1-Pad30)") (class "Default")
      (node (ref "U1") (pin "30") (pinfunction "PA9/PGMM1_30") (pintype "bidirectional"))
    )
    (net (code "61") (name "unconnected-(U1A-PA15{slash}PGMD3-Pad20)") (class "Default")
      (node (ref "U1") (pin "20") (pinfunction "PA15/PGMD3_20") (pintype "bidirectional"))
    )
    (net (code "62") (name "unconnected-(U1A-PA16{slash}PGMD4-Pad19)") (class "Default")
      (node (ref "U1") (pin "19") (pinfunction "PA16/PGMD4_19") (pintype "bidirectional"))
    )
    (net (code "63") (name "unconnected-(U1A-PA17{slash}PGMD5{slash}AD0-Pad9)") (class "Default")
      (node (ref "U1") (pin "9") (pinfunction "PA17/PGMD5/AD0_9") (pintype "bidirectional"))
    )
    (net (code "64") (name "unconnected-(U1A-PA18{slash}PGMD6{slash}AD1-Pad10)") (class "Default")
      (node (ref "U1") (pin "10") (pinfunction "PA18/PGMD6/AD1_10") (pintype "bidirectional"))
    )
    (net (code "65") (name "unconnected-(U1A-PA24{slash}PGMD12-Pad23)") (class "Default")
      (node (ref "U1") (pin "23") (pinfunction "PA24/PGMD12_23") (pintype "bidirectional"))
    )
    (net (code "66") (name "unconnected-(U1A-PA29-Pad41)") (class "Default")
      (node (ref "U1") (pin "41") (pinfunction "PA29_41") (pintype "bidirectional"))
    )
    (net (code "67") (name "unconnected-(U1A-PA30-Pad42)") (class "Default")
      (node (ref "U1") (pin "42") (pinfunction "PA30_42") (pintype "bidirectional"))
    )
    (net (code "68") (name "unconnected-(U1A-PA31-Pad52)") (class "Default")
      (node (ref "U1") (pin "52") (pinfunction "PA31_52") (pintype "bidirectional"))
    )
    (net (code "69") (name "unconnected-(U1A-PB3{slash}AD7-Pad6)") (class "Default")
      (node (ref "U1") (pin "6") (pinfunction "PB3/AD7_6") (pintype "bidirectional"))
    )
    (net (code "70") (name "unconnected-(U1A-PB14{slash}DAC1-Pad63)") (class "Default")
      (node (ref "U1") (pin "63") (pinfunction "PB14/DAC1_63") (pintype "bidirectional"))
    )
    (net (code "71") (name "unconnected-(U1A-TDO{slash}TRACESWO{slash}PB5-Pad49)") (class "Default")
      (node (ref "U1") (pin "49") (pinfunction "TDO/TRACESWO/PB5_49") (pintype "bidirectional"))
    )
    (net (code "72") (name "unconnected-(U1A-TST-Pad40)") (class "Default")
      (node (ref "U1") (pin "40") (pinfunction "TST_40") (pintype "input+no_connect"))
    )
    (net (code "73") (name "unconnected-(U2-BYP-Pad4)") (class "Default")
      (node (ref "U2") (pin "4") (pinfunction "BYP_4") (pintype "passive+no_connect"))
    )
  )
)
